# CAN_Connections.net
KiCad netlist of a schematic drawn in Altium Designer
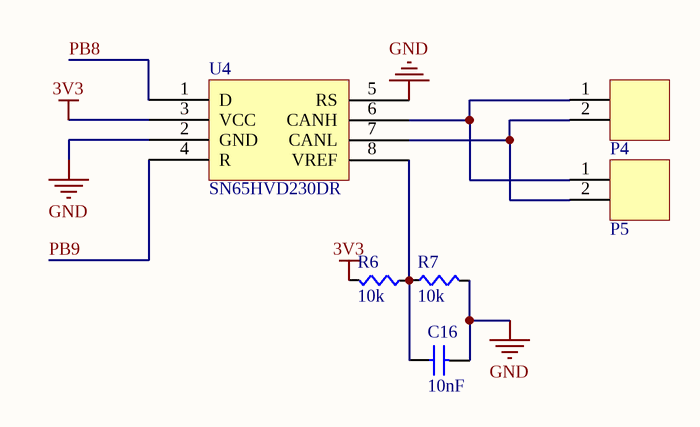
[diagram p0: CAN_Connections.SchDoc]

(export (version "E")
  (design (tool "Eeschema 10.0.6"))
  (components
    (comp (ref "C16")
      (value "10nF")
      (footprint "CAPC0603")
      (fields (field (name "Comment") "Cap"))
      (libsource (lib "SubjuGator8") (part "Cap"))
    )
    (comp (ref "P4")
      (value "2-pin Horz Sherlock")
      (footprint "MOLEX-HDR-1X2-SHERLOCK-HORZ")
      (fields
        (field (name "MANUFACTURER PART NUMBER") "0353630260")
        (field (name "MANUFACTURER") "Molex Inc")
      )
      (libsource (lib "SubjuGator8") (part "MOLEX-HDR-1x2-SHERLOCK_RA"))
    )
    (comp (ref "P5")
      (value "2-pin Horz Sherlock")
      (footprint "MOLEX-HDR-1X2-SHERLOCK-HORZ")
      (fields
        (field (name "MANUFACTURER PART NUMBER") "0353630260")
        (field (name "MANUFACTURER") "Molex Inc")
      )
      (libsource (lib "SubjuGator8") (part "MOLEX-HDR-1x2-SHERLOCK_RA"))
    )
    (comp (ref "R6")
      (value "10k")
      (footprint "RES0603")
      (fields (field (name "Comment") "Res"))
      (libsource (lib "SubjuGator8") (part "Res"))
    )
    (comp (ref "R7")
      (value "10k")
      (footprint "RES0603")
      (fields (field (name "Comment") "Res"))
      (libsource (lib "SubjuGator8") (part "Res"))
    )
    (comp (ref "U4")
      (value "SN65HVD230DR")
      (footprint "SOIC-8pin")
      (description "IC TXRX CAN 1MBPS 3.3V 8SOIC")
      (libsource (lib "SubjuGator8") (part "SN65HVD230DR"))
    )
  )
  (nets
    (net (code "1") (name "/PB8") (class "Default")
      (node (ref "U4") (pin "1") (pinfunction "D_1") (pintype "passive"))
    )
    (net (code "2") (name "/PB9") (class "Default")
      (node (ref "U4") (pin "4") (pinfunction "R_4") (pintype "passive"))
    )
    (net (code "3") (name "3V3") (class "Default")
      (node (ref "R6") (pin "1") (pinfunction "A_1") (pintype "passive"))
      (node (ref "U4") (pin "3") (pinfunction "VCC_3") (pintype "passive"))
    )
    (net (code "4") (name "GND") (class "Default")
      (node (ref "C16") (pin "2") (pinfunction "B_2") (pintype "passive"))
      (node (ref "R7") (pin "1") (pinfunction "A_1") (pintype "passive"))
      (node (ref "U4") (pin "2") (pinfunction "GND_2") (pintype "passive"))
      (node (ref "U4") (pin "5") (pinfunction "RS_5") (pintype "passive"))
    )
    (net (code "5") (name "Net-(C16-A)") (class "Default")
      (node (ref "C16") (pin "1") (pinfunction "A_1") (pintype "passive"))
      (node (ref "R6") (pin "2") (pinfunction "B_2") (pintype "passive"))
      (node (ref "R7") (pin "2") (pinfunction "B_2") (pintype "passive"))
      (node (ref "U4") (pin "8") (pinfunction "VREF_8") (pintype "passive"))
    )
    (net (code "6") (name "Net-(U4-CANH)") (class "Default")
      (node (ref "P4") (pin "1") (pinfunction "1_1") (pintype "passive"))
      (node (ref "P5") (pin "1") (pinfunction "1_1") (pintype "passive"))
      (node (ref "U4") (pin "6") (pinfunction "CANH_6") (pintype "passive"))
    )
    (net (code "7") (name "Net-(U4-CANL)") (class "Default")
      (node (ref "P4") (pin "2") (pinfunction "2_2") (pintype "passive"))
      (node (ref "P5") (pin "2") (pinfunction "2_2") (pintype "passive"))
      (node (ref "U4") (pin "7") (pinfunction "CANL_7") (pintype "passive"))
    )
  )
)
